# Skey.net
KiCad netlist of a schematic drawn in Altium Designer
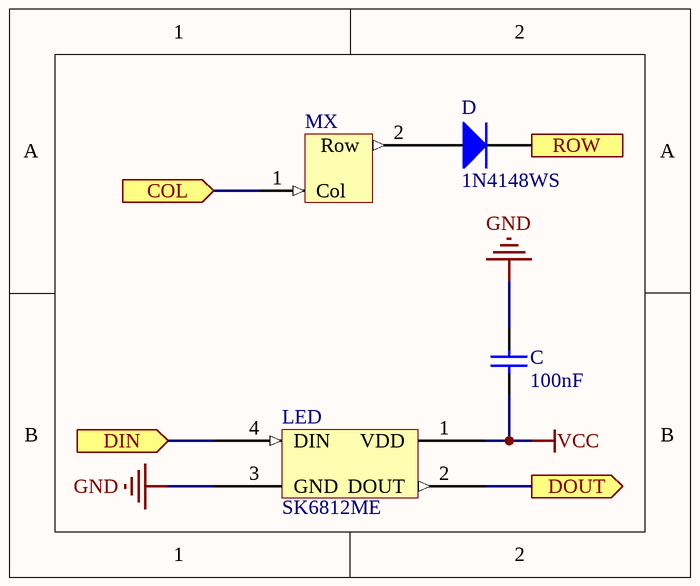
[diagram p0: Skey.SchDoc]

(export (version "E")
  (design (tool "Eeschema 10.0.6"))
  (components
    (comp (ref "C")
      (value "100nF")
      (footprint "CAPC1005X55X30LL05T10")
      (fields (field (name "MANUFACTURER") "Kemet") (field (name "PART NUMBER") "C0402C104K4RACTU"))
      (libsource (lib "Altium Content Vault") (part "CAP"))
    )
    (comp (ref "D")
      (value "1N4148WS")
      (footprint "DIOD-SOD323-2-A_V")
      (description "Fast Switching Diode, 75 V, 0.3 A, -65 to 150 degC, 2-Pin SOD323, RoHS, Tape and Reel")
      (libsource (lib "Altium Content Vault") (part "D-AK-2"))
    )
    (comp (ref "LED")
      (value "SK6812ME")
      (footprint "SK6812ME")
      (description "Individually Adressable SK6812 Mini-E 3528 LED")
      (libsource (lib "Skayboard") (part "SK6812"))
    )
    (comp (ref "MX")
      (value "~")
      (footprint "MX")
      (description "Cherry MX Footprint")
      (libsource (lib "Skayboard") (part "MX"))
    )
  )
  (nets
    (net (code "1") (name "/COL") (class "Default")
      (node (ref "MX") (pin "1") (pinfunction "Col_1") (pintype "input"))
    )
    (net (code "2") (name "/DIN") (class "Default")
      (node (ref "LED") (pin "4") (pinfunction "DIN_4") (pintype "input"))
    )
    (net (code "3") (name "/DOUT") (class "Default")
      (node (ref "LED") (pin "2") (pinfunction "DOUT_2") (pintype "output"))
    )
    (net (code "4") (name "/ROW") (class "Default")
      (node (ref "D") (pin "2") (pinfunction "K_2") (pintype "passive"))
    )
    (net (code "5") (name "GND") (class "Default")
      (node (ref "C") (pin "2") (pinfunction "2_2") (pintype "passive"))
      (node (ref "LED") (pin "3") (pinfunction "GND_3") (pintype "power_in"))
    )
    (net (code "6") (name "Net-(D-A)") (class "Default")
      (node (ref "D") (pin "1") (pinfunction "A_1") (pintype "passive"))
      (node (ref "MX") (pin "2") (pinfunction "Row_2") (pintype "output"))
    )
    (net (code "7") (name "VCC") (class "Default")
      (node (ref "C") (pin "1") (pinfunction "1_1") (pintype "passive"))
      (node (ref "LED") (pin "1") (pinfunction "VDD_1") (pintype "power_in"))
    )
  )
)
